# usb-hub-v0_4.net
KiCad netlist of a schematic drawn in EAGLE
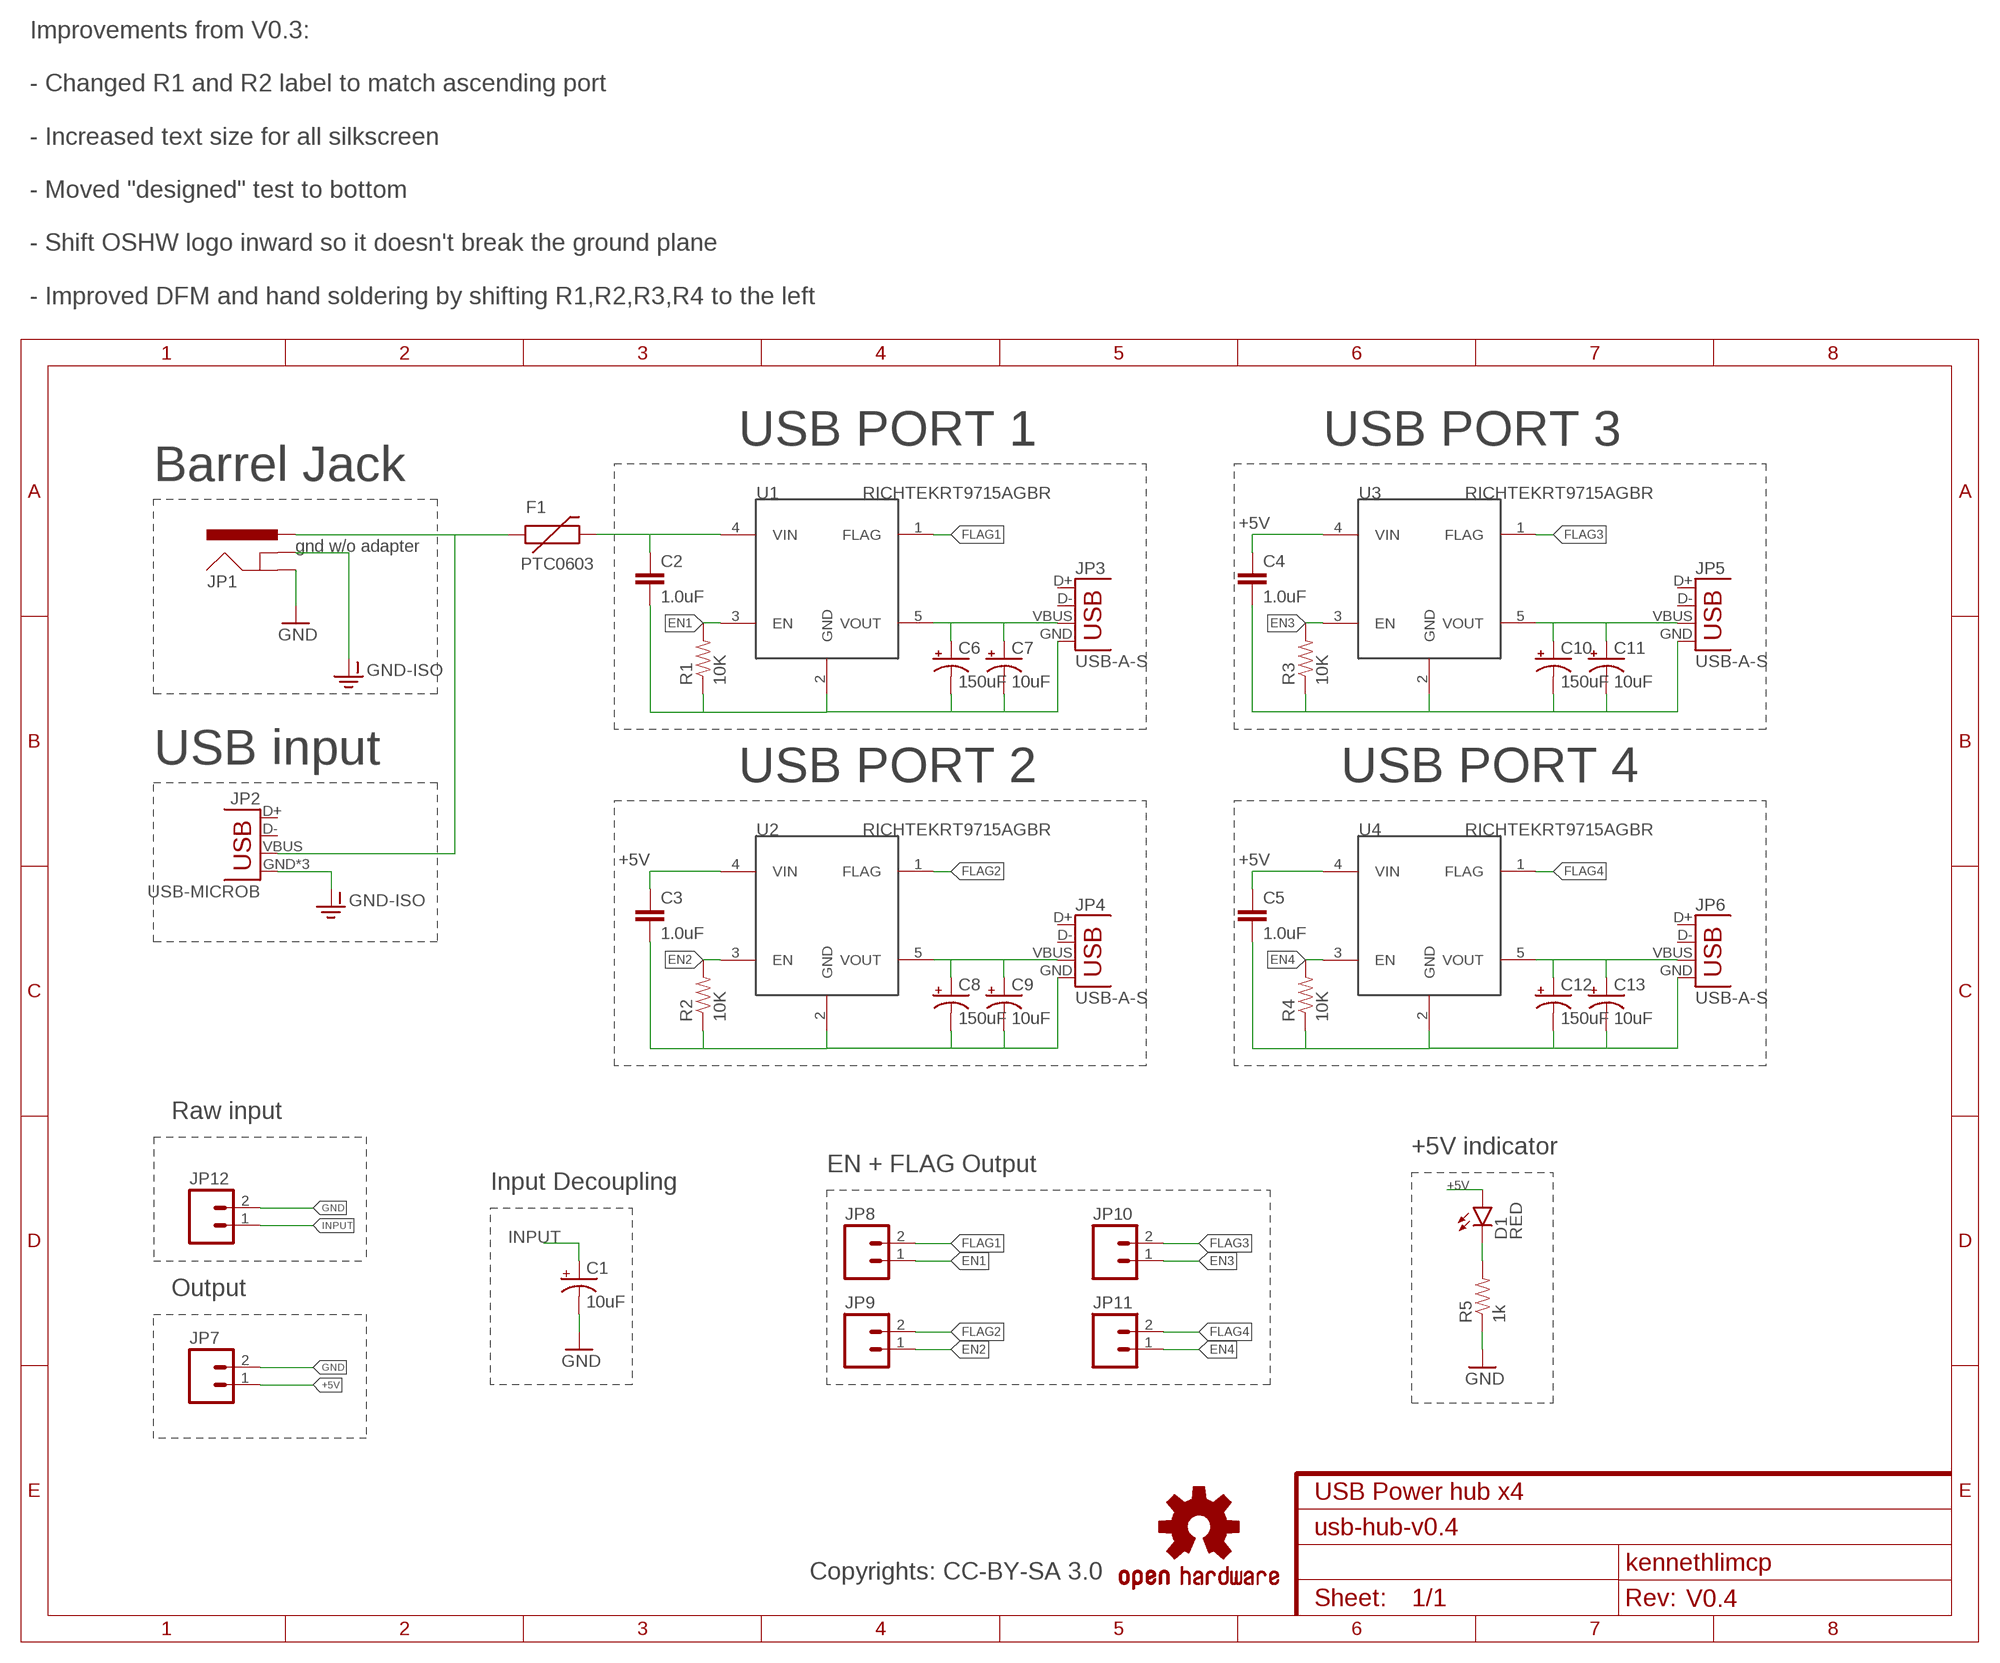
[diagram p0: schematic, sheet 1]

(export (version "E")
  (design (tool "Eeschema 10.0.6"))
  (components
    (comp (ref "C1")
      (value "10uF")
      (footprint "eagle-import:EIA3216")
      (libsource (lib "eagle-import") (part "10UF-16V-10%(TANT)"))
    )
    (comp (ref "C2")
      (value "1.0uF")
      (footprint "eagle-import:0603-CAP")
      (libsource (lib "eagle-import") (part "1.0UF-16V-10%(0603)"))
    )
    (comp (ref "C3")
      (value "1.0uF")
      (footprint "eagle-import:0603-CAP")
      (libsource (lib "eagle-import") (part "1.0UF-16V-10%(0603)"))
    )
    (comp (ref "C4")
      (value "1.0uF")
      (footprint "eagle-import:0603-CAP")
      (libsource (lib "eagle-import") (part "1.0UF-16V-10%(0603)"))
    )
    (comp (ref "C5")
      (value "1.0uF")
      (footprint "eagle-import:0603-CAP")
      (libsource (lib "eagle-import") (part "1.0UF-16V-10%(0603)"))
    )
    (comp (ref "C6")
      (value "150uF")
      (footprint "eagle-import:PANASONIC_D")
      (libsource (lib "eagle-import") (part "CAP_POLD"))
    )
    (comp (ref "C7")
      (value "10uF")
      (footprint "eagle-import:EIA3216")
      (libsource (lib "eagle-import") (part "10UF-16V-10%(TANT)"))
    )
    (comp (ref "C8")
      (value "150uF")
      (footprint "eagle-import:PANASONIC_D")
      (libsource (lib "eagle-import") (part "CAP_POLD"))
    )
    (comp (ref "C9")
      (value "10uF")
      (footprint "eagle-import:EIA3216")
      (libsource (lib "eagle-import") (part "10UF-16V-10%(TANT)"))
    )
    (comp (ref "C10")
      (value "150uF")
      (footprint "eagle-import:PANASONIC_D")
      (libsource (lib "eagle-import") (part "CAP_POLD"))
    )
    (comp (ref "C11")
      (value "10uF")
      (footprint "eagle-import:EIA3216")
      (libsource (lib "eagle-import") (part "10UF-16V-10%(TANT)"))
    )
    (comp (ref "C12")
      (value "150uF")
      (footprint "eagle-import:PANASONIC_D")
      (libsource (lib "eagle-import") (part "CAP_POLD"))
    )
    (comp (ref "C13")
      (value "10uF")
      (footprint "eagle-import:EIA3216")
      (libsource (lib "eagle-import") (part "10UF-16V-10%(TANT)"))
    )
    (comp (ref "D1")
      (value "RED")
      (footprint "eagle-import:LED-0603")
      (libsource (lib "eagle-import") (part "LED-RED0603"))
    )
    (comp (ref "F1")
      (value "PTC0603")
      (footprint "eagle-import:0603")
      (libsource (lib "eagle-import") (part "PTC0603"))
    )
    (comp (ref "JP1")
      (value "POWER_JACKPTH_LOCK")
      (footprint "eagle-import:POWER_JACK_PTH_LOCK")
      (libsource (lib "eagle-import") (part "POWER_JACKPTH_LOCK"))
    )
    (comp (ref "JP2")
      (value "USB-MICROB")
      (footprint "eagle-import:USB-MICROB")
      (libsource (lib "eagle-import") (part "USB-MICROB"))
    )
    (comp (ref "JP3")
      (value "USB-A-S")
      (footprint "eagle-import:USB-A-S")
      (libsource (lib "eagle-import") (part "USB-A-S"))
    )
    (comp (ref "JP4")
      (value "USB-A-S")
      (footprint "eagle-import:USB-A-S")
      (libsource (lib "eagle-import") (part "USB-A-S"))
    )
    (comp (ref "JP5")
      (value "USB-A-S")
      (footprint "eagle-import:USB-A-S")
      (libsource (lib "eagle-import") (part "USB-A-S"))
    )
    (comp (ref "JP6")
      (value "USB-A-S")
      (footprint "eagle-import:USB-A-S")
      (libsource (lib "eagle-import") (part "USB-A-S"))
    )
    (comp (ref "JP7")
      (value "M02PTH")
      (footprint "eagle-import:1X02")
      (libsource (lib "eagle-import") (part "M02PTH"))
    )
    (comp (ref "JP8")
      (value "M02PTH")
      (footprint "eagle-import:1X02")
      (libsource (lib "eagle-import") (part "M02PTH"))
    )
    (comp (ref "JP9")
      (value "M02PTH")
      (footprint "eagle-import:1X02")
      (libsource (lib "eagle-import") (part "M02PTH"))
    )
    (comp (ref "JP10")
      (value "M02PTH")
      (footprint "eagle-import:1X02")
      (libsource (lib "eagle-import") (part "M02PTH"))
    )
    (comp (ref "JP11")
      (value "M02PTH")
      (footprint "eagle-import:1X02")
      (libsource (lib "eagle-import") (part "M02PTH"))
    )
    (comp (ref "JP12")
      (value "M02PTH")
      (footprint "eagle-import:1X02")
      (libsource (lib "eagle-import") (part "M02PTH"))
    )
    (comp (ref "LOGO1")
      (value "OSHW-LOGOPAD")
      (footprint "eagle-import:OSHW-LOGO-M-PAD")
      (libsource (lib "eagle-import") (part "OSHW-LOGOPAD"))
    )
    (comp (ref "R1")
      (value "10K")
      (footprint "eagle-import:0402-RES")
      (libsource (lib "eagle-import") (part "RESISTOR0402"))
    )
    (comp (ref "R2")
      (value "10K")
      (footprint "eagle-import:0402-RES")
      (libsource (lib "eagle-import") (part "RESISTOR0402"))
    )
    (comp (ref "R3")
      (value "10K")
      (footprint "eagle-import:0402-RES")
      (libsource (lib "eagle-import") (part "RESISTOR0402"))
    )
    (comp (ref "R4")
      (value "10K")
      (footprint "eagle-import:0402-RES")
      (libsource (lib "eagle-import") (part "RESISTOR0402"))
    )
    (comp (ref "R5")
      (value "1k")
      (footprint "eagle-import:0402-RES")
      (libsource (lib "eagle-import") (part "RESISTOR0402"))
    )
    (comp (ref "U1")
      (value "RICHTEKRT9715AGBR")
      (footprint "eagle-import:SOT23-5")
      (libsource (lib "eagle-import") (part "RICHTEKRT9715AGBR"))
    )
    (comp (ref "U2")
      (value "RICHTEKRT9715AGBR")
      (footprint "eagle-import:SOT23-5")
      (libsource (lib "eagle-import") (part "RICHTEKRT9715AGBR"))
    )
    (comp (ref "U3")
      (value "RICHTEKRT9715AGBR")
      (footprint "eagle-import:SOT23-5")
      (libsource (lib "eagle-import") (part "RICHTEKRT9715AGBR"))
    )
    (comp (ref "U4")
      (value "RICHTEKRT9715AGBR")
      (footprint "eagle-import:SOT23-5")
      (libsource (lib "eagle-import") (part "RICHTEKRT9715AGBR"))
    )
  )
  (nets
    (net (code "1") (name "+5V") (class "Default")
      (node (ref "C2") (pin "1") (pinfunction "1_1") (pintype "passive"))
      (node (ref "C3") (pin "1") (pinfunction "1_1") (pintype "passive"))
      (node (ref "C4") (pin "1") (pinfunction "1_1") (pintype "passive"))
      (node (ref "C5") (pin "1") (pinfunction "1_1") (pintype "passive"))
      (node (ref "D1") (pin "A") (pinfunction "A_A") (pintype "passive"))
      (node (ref "F1") (pin "2") (pinfunction "2_2") (pintype "bidirectional"))
      (node (ref "JP7") (pin "1") (pinfunction "1_1") (pintype "passive"))
      (node (ref "U1") (pin "4") (pinfunction "VIN_4") (pintype "bidirectional"))
      (node (ref "U2") (pin "4") (pinfunction "VIN_4") (pintype "bidirectional"))
      (node (ref "U3") (pin "4") (pinfunction "VIN_4") (pintype "bidirectional"))
      (node (ref "U4") (pin "4") (pinfunction "VIN_4") (pintype "bidirectional"))
    )
    (net (code "2") (name "EN1") (class "Default")
      (node (ref "JP8") (pin "1") (pinfunction "1_1") (pintype "passive"))
      (node (ref "R1") (pin "2") (pinfunction "2_2") (pintype "passive"))
      (node (ref "U1") (pin "3") (pinfunction "EN_3") (pintype "bidirectional"))
    )
    (net (code "3") (name "EN2") (class "Default")
      (node (ref "JP9") (pin "1") (pinfunction "1_1") (pintype "passive"))
      (node (ref "R2") (pin "2") (pinfunction "2_2") (pintype "passive"))
      (node (ref "U2") (pin "3") (pinfunction "EN_3") (pintype "bidirectional"))
    )
    (net (code "4") (name "EN3") (class "Default")
      (node (ref "JP10") (pin "1") (pinfunction "1_1") (pintype "passive"))
      (node (ref "R3") (pin "2") (pinfunction "2_2") (pintype "passive"))
      (node (ref "U3") (pin "3") (pinfunction "EN_3") (pintype "bidirectional"))
    )
    (net (code "5") (name "EN4") (class "Default")
      (node (ref "JP11") (pin "1") (pinfunction "1_1") (pintype "passive"))
      (node (ref "R4") (pin "2") (pinfunction "2_2") (pintype "passive"))
      (node (ref "U4") (pin "3") (pinfunction "EN_3") (pintype "bidirectional"))
    )
    (net (code "6") (name "FLAG1") (class "Default")
      (node (ref "JP8") (pin "2") (pinfunction "2_2") (pintype "passive"))
      (node (ref "U1") (pin "1") (pinfunction "FLAG_1") (pintype "bidirectional"))
    )
    (net (code "7") (name "FLAG2") (class "Default")
      (node (ref "JP9") (pin "2") (pinfunction "2_2") (pintype "passive"))
      (node (ref "U2") (pin "1") (pinfunction "FLAG_1") (pintype "bidirectional"))
    )
    (net (code "8") (name "FLAG3") (class "Default")
      (node (ref "JP10") (pin "2") (pinfunction "2_2") (pintype "passive"))
      (node (ref "U3") (pin "1") (pinfunction "FLAG_1") (pintype "bidirectional"))
    )
    (net (code "9") (name "FLAG4") (class "Default")
      (node (ref "JP11") (pin "2") (pinfunction "2_2") (pintype "passive"))
      (node (ref "U4") (pin "1") (pinfunction "FLAG_1") (pintype "bidirectional"))
    )
    (net (code "10") (name "GND") (class "Default")
      (node (ref "C1") (pin "C") (pinfunction "-_C") (pintype "passive"))
      (node (ref "C10") (pin "-") (pinfunction "-_-") (pintype "passive"))
      (node (ref "C11") (pin "C") (pinfunction "-_C") (pintype "passive"))
      (node (ref "C12") (pin "-") (pinfunction "-_-") (pintype "passive"))
      (node (ref "C13") (pin "C") (pinfunction "-_C") (pintype "passive"))
      (node (ref "C2") (pin "2") (pinfunction "2_2") (pintype "passive"))
      (node (ref "C3") (pin "2") (pinfunction "2_2") (pintype "passive"))
      (node (ref "C4") (pin "2") (pinfunction "2_2") (pintype "passive"))
      (node (ref "C5") (pin "2") (pinfunction "2_2") (pintype "passive"))
      (node (ref "C6") (pin "-") (pinfunction "-_-") (pintype "passive"))
      (node (ref "C7") (pin "C") (pinfunction "-_C") (pintype "passive"))
      (node (ref "C8") (pin "-") (pinfunction "-_-") (pintype "passive"))
      (node (ref "C9") (pin "C") (pinfunction "-_C") (pintype "passive"))
      (node (ref "JP1") (pin "GND") (pinfunction "GND_GND") (pintype "bidirectional"))
      (node (ref "JP12") (pin "2") (pinfunction "2_2") (pintype "passive"))
      (node (ref "JP3") (pin "GND") (pinfunction "GND_GND") (pintype "bidirectional"))
      (node (ref "JP4") (pin "GND") (pinfunction "GND_GND") (pintype "bidirectional"))
      (node (ref "JP5") (pin "GND") (pinfunction "GND_GND") (pintype "bidirectional"))
      (node (ref "JP6") (pin "GND") (pinfunction "GND_GND") (pintype "bidirectional"))
      (node (ref "JP7") (pin "2") (pinfunction "2_2") (pintype "passive"))
      (node (ref "R1") (pin "1") (pinfunction "1_1") (pintype "passive"))
      (node (ref "R2") (pin "1") (pinfunction "1_1") (pintype "passive"))
      (node (ref "R3") (pin "1") (pinfunction "1_1") (pintype "passive"))
      (node (ref "R4") (pin "1") (pinfunction "1_1") (pintype "passive"))
      (node (ref "R5") (pin "1") (pinfunction "1_1") (pintype "passive"))
      (node (ref "U1") (pin "2") (pinfunction "GND_2") (pintype "bidirectional"))
      (node (ref "U2") (pin "2") (pinfunction "GND_2") (pintype "bidirectional"))
      (node (ref "U3") (pin "2") (pinfunction "GND_2") (pintype "bidirectional"))
      (node (ref "U4") (pin "2") (pinfunction "GND_2") (pintype "bidirectional"))
    )
    (net (code "11") (name "GND-ISO") (class "Default")
      (node (ref "JP1") (pin "GNDBREAK") (pinfunction "GNDBREAK_GNDBREAK") (pintype "bidirectional"))
      (node (ref "JP2") (pin "GND") (pinfunction "GND_GND") (pintype "bidirectional"))
      (node (ref "JP2") (pin "MT1") (pinfunction "GND_MT1") (pintype "bidirectional"))
      (node (ref "JP2") (pin "MT2") (pinfunction "GND_MT2") (pintype "bidirectional"))
    )
    (net (code "12") (name "INPUT") (class "Default")
      (node (ref "C1") (pin "A") (pinfunction "+_A") (pintype "passive"))
      (node (ref "F1") (pin "1") (pinfunction "1_1") (pintype "bidirectional"))
      (node (ref "JP1") (pin "PWR") (pinfunction "PWR_PWR") (pintype "bidirectional"))
      (node (ref "JP12") (pin "1") (pinfunction "1_1") (pintype "passive"))
      (node (ref "JP2") (pin "VBUS") (pinfunction "VBUS_VBUS") (pintype "bidirectional"))
    )
    (net (code "13") (name "Net-(C7-+)") (class "Default")
      (node (ref "C6") (pin "+") (pinfunction "+_+") (pintype "passive"))
      (node (ref "C7") (pin "A") (pinfunction "+_A") (pintype "passive"))
      (node (ref "JP3") (pin "VBUS") (pinfunction "VBUS_VBUS") (pintype "bidirectional"))
      (node (ref "U1") (pin "5") (pinfunction "VOUT_5") (pintype "bidirectional"))
    )
    (net (code "14") (name "Net-(C9-+)") (class "Default")
      (node (ref "C8") (pin "+") (pinfunction "+_+") (pintype "passive"))
      (node (ref "C9") (pin "A") (pinfunction "+_A") (pintype "passive"))
      (node (ref "JP4") (pin "VBUS") (pinfunction "VBUS_VBUS") (pintype "bidirectional"))
      (node (ref "U2") (pin "5") (pinfunction "VOUT_5") (pintype "bidirectional"))
    )
    (net (code "15") (name "Net-(C11-+)") (class "Default")
      (node (ref "C10") (pin "+") (pinfunction "+_+") (pintype "passive"))
      (node (ref "C11") (pin "A") (pinfunction "+_A") (pintype "passive"))
      (node (ref "JP5") (pin "VBUS") (pinfunction "VBUS_VBUS") (pintype "bidirectional"))
      (node (ref "U3") (pin "5") (pinfunction "VOUT_5") (pintype "bidirectional"))
    )
    (net (code "16") (name "Net-(C13-+)") (class "Default")
      (node (ref "C12") (pin "+") (pinfunction "+_+") (pintype "passive"))
      (node (ref "C13") (pin "A") (pinfunction "+_A") (pintype "passive"))
      (node (ref "JP6") (pin "VBUS") (pinfunction "VBUS_VBUS") (pintype "bidirectional"))
      (node (ref "U4") (pin "5") (pinfunction "VOUT_5") (pintype "bidirectional"))
    )
    (net (code "17") (name "Net-(D1-PadC)") (class "Default")
      (node (ref "D1") (pin "C") (pinfunction "C_C") (pintype "passive"))
      (node (ref "R5") (pin "2") (pinfunction "2_2") (pintype "passive"))
    )
    (net (code "18") (name "unconnected-(JP2-PadD+)") (class "Default")
      (node (ref "JP2") (pin "D+") (pinfunction "D+_D+") (pintype "bidirectional"))
    )
    (net (code "19") (name "unconnected-(JP2-PadD-)") (class "Default")
      (node (ref "JP2") (pin "D-") (pinfunction "D-_D-") (pintype "bidirectional"))
    )
    (net (code "20") (name "unconnected-(JP3-PadD+)") (class "Default")
      (node (ref "JP3") (pin "D+") (pinfunction "D+_D+") (pintype "bidirectional"))
    )
    (net (code "21") (name "unconnected-(JP3-PadD-)") (class "Default")
      (node (ref "JP3") (pin "D-") (pinfunction "D-_D-") (pintype "bidirectional"))
    )
    (net (code "22") (name "unconnected-(JP4-PadD+)") (class "Default")
      (node (ref "JP4") (pin "D+") (pinfunction "D+_D+") (pintype "bidirectional"))
    )
    (net (code "23") (name "unconnected-(JP4-PadD-)") (class "Default")
      (node (ref "JP4") (pin "D-") (pinfunction "D-_D-") (pintype "bidirectional"))
    )
    (net (code "24") (name "unconnected-(JP5-PadD+)") (class "Default")
      (node (ref "JP5") (pin "D+") (pinfunction "D+_D+") (pintype "bidirectional"))
    )
    (net (code "25") (name "unconnected-(JP5-PadD-)") (class "Default")
      (node (ref "JP5") (pin "D-") (pinfunction "D-_D-") (pintype "bidirectional"))
    )
    (net (code "26") (name "unconnected-(JP6-PadD+)") (class "Default")
      (node (ref "JP6") (pin "D+") (pinfunction "D+_D+") (pintype "bidirectional"))
    )
    (net (code "27") (name "unconnected-(JP6-PadD-)") (class "Default")
      (node (ref "JP6") (pin "D-") (pinfunction "D-_D-") (pintype "bidirectional"))
    )
  )
)
